# 15_HEATER.net
KiCad netlist of a schematic drawn in Altium Designer
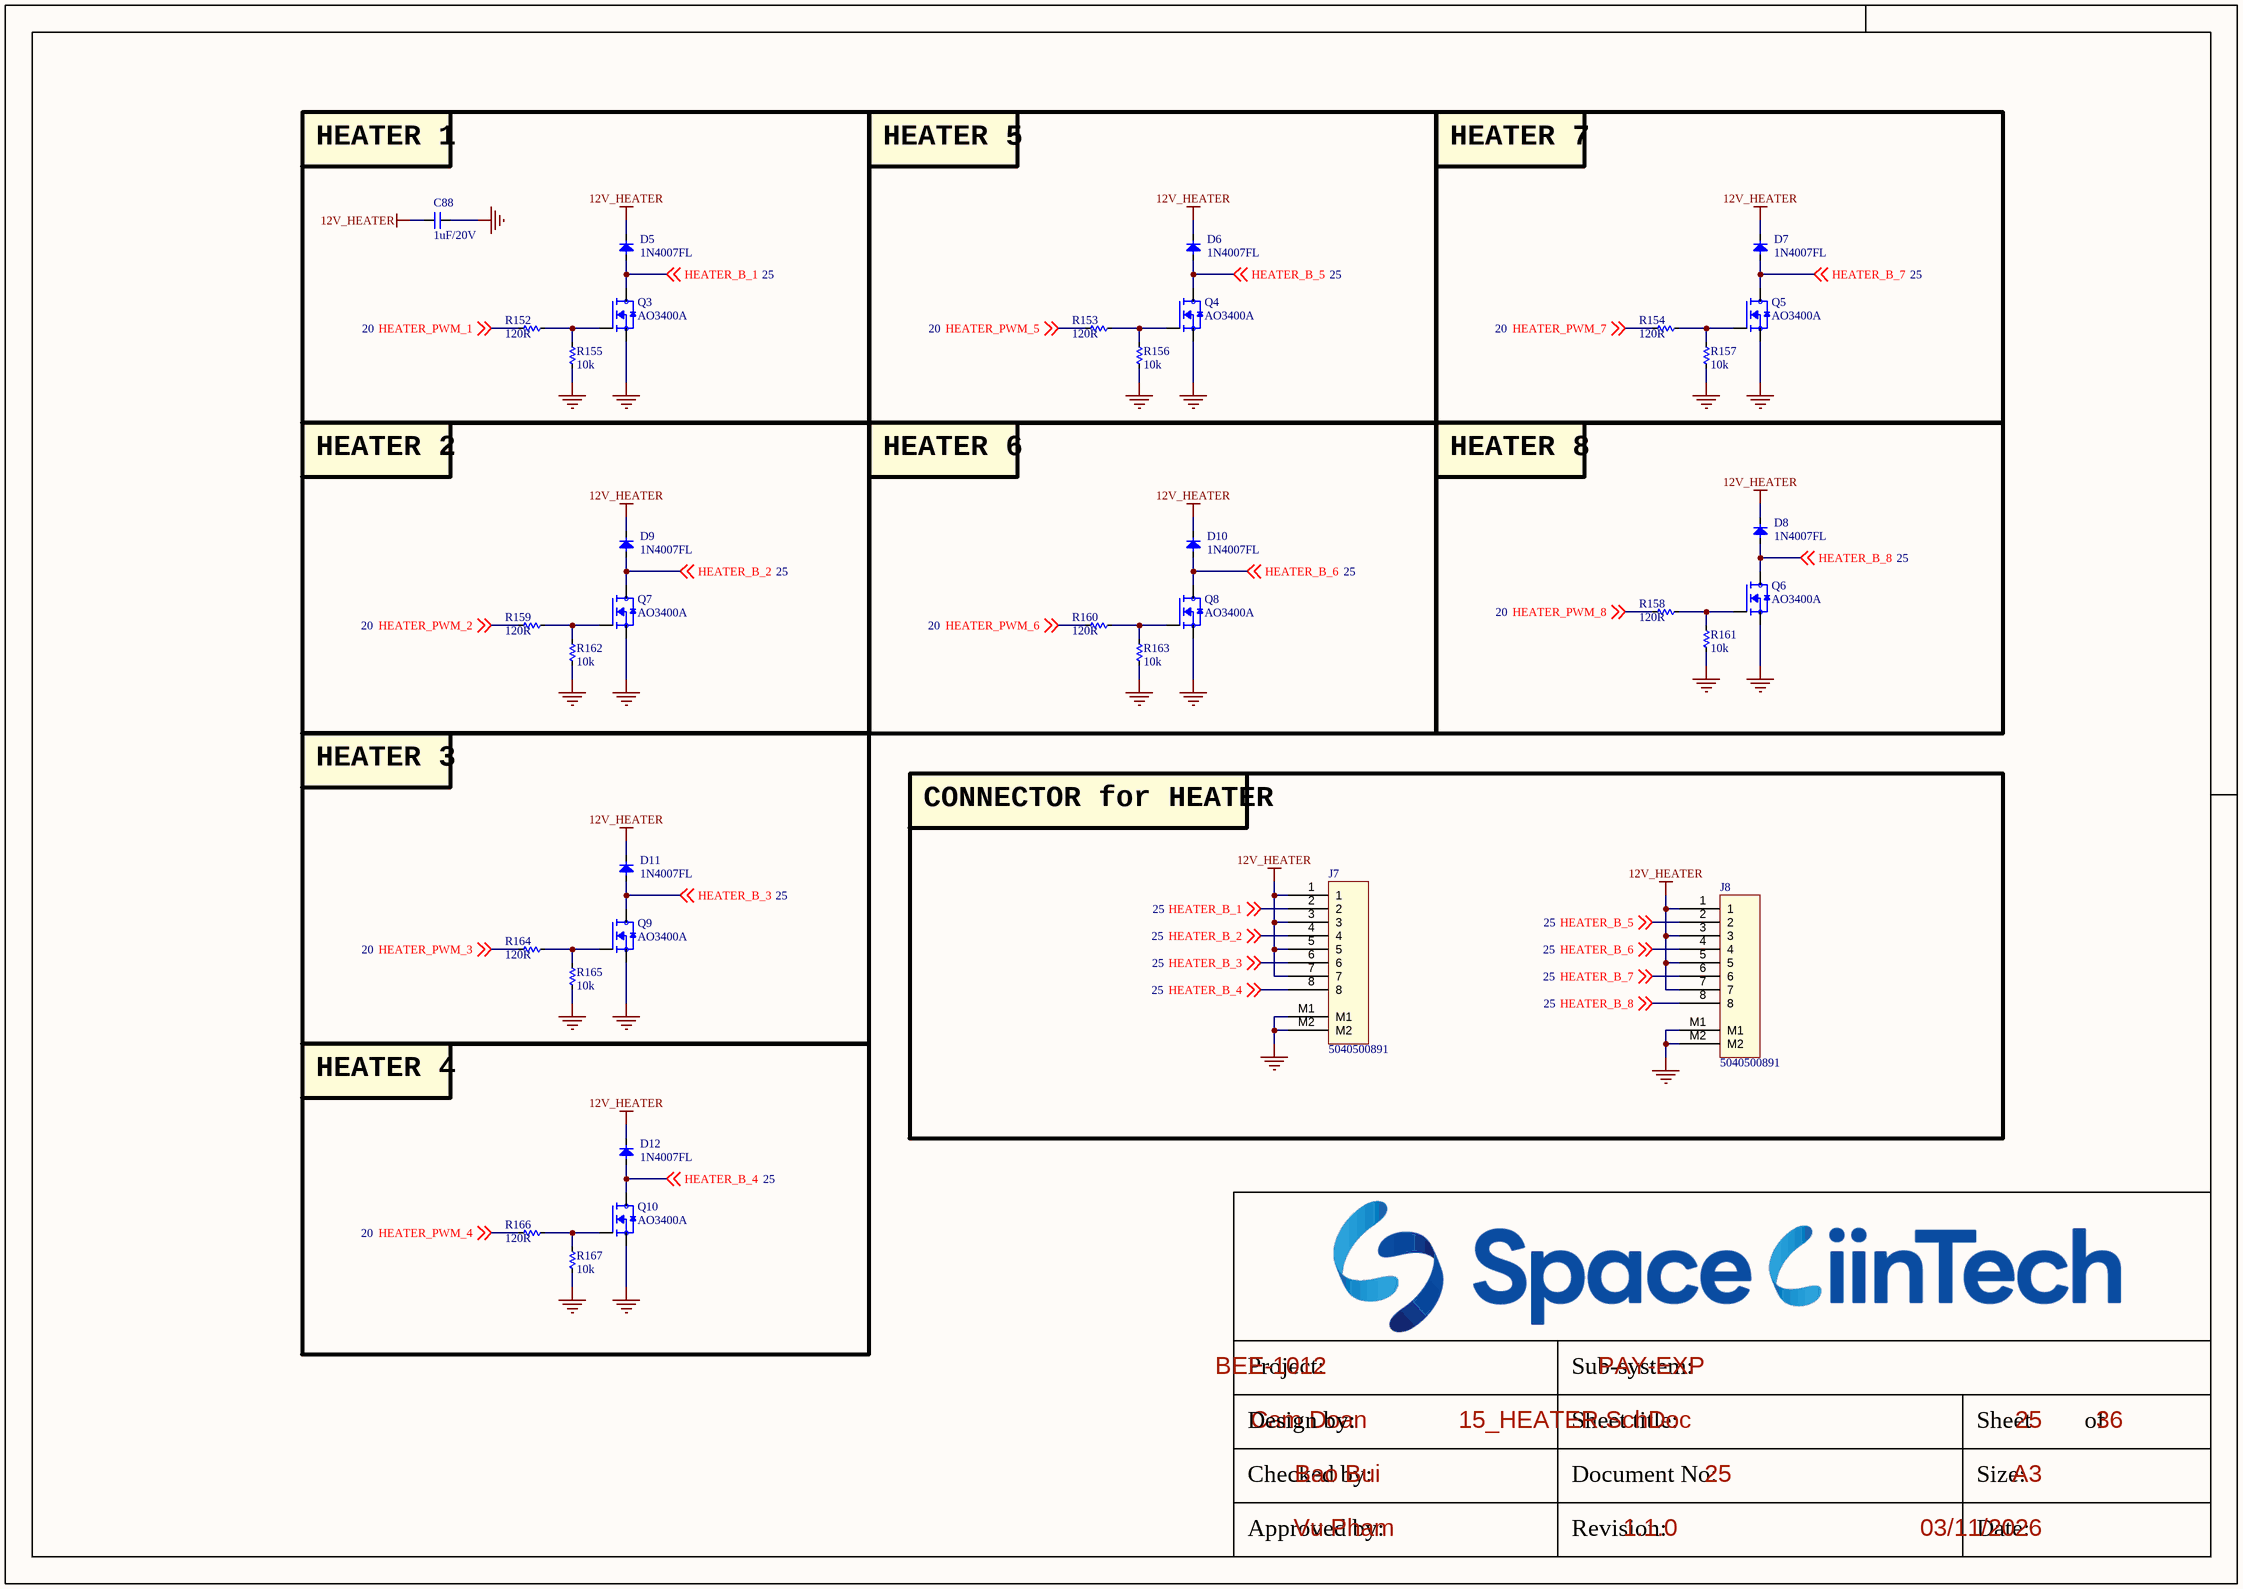
[diagram p0: 15_HEATER.SchDoc]

(export (version "E")
  (design (tool "Eeschema 10.0.6"))
  (components
    (comp (ref "C88")
      (value "1uF/20V")
      (footprint "CAP_C_1005X50_L")
      (description "CAP")
      (libsource (lib "LABLIB") (part "_CAP_C_2"))
    )
    (comp (ref "D5")
      (value "1N4007FL")
      (footprint "SOD3717X145N")
      (description "Default Diode")
      (fields (field (name "PUBLISHER") "Altium Limited"))
      (libsource (lib "LABLIB") (part "Diode SMD"))
    )
    (comp (ref "D6")
      (value "1N4007FL")
      (footprint "SOD3717X145N")
      (description "Default Diode")
      (fields (field (name "PUBLISHER") "Altium Limited"))
      (libsource (lib "LABLIB") (part "Diode SMD"))
    )
    (comp (ref "D7")
      (value "1N4007FL")
      (footprint "SOD3717X145N")
      (description "Default Diode")
      (fields (field (name "PUBLISHER") "Altium Limited"))
      (libsource (lib "LABLIB") (part "Diode SMD"))
    )
    (comp (ref "D8")
      (value "1N4007FL")
      (footprint "SOD3717X145N")
      (description "Default Diode")
      (fields (field (name "PUBLISHER") "Altium Limited"))
      (libsource (lib "LABLIB") (part "Diode SMD"))
    )
    (comp (ref "D9")
      (value "1N4007FL")
      (footprint "SOD3717X145N")
      (description "Default Diode")
      (fields (field (name "PUBLISHER") "Altium Limited"))
      (libsource (lib "LABLIB") (part "Diode SMD"))
    )
    (comp (ref "D10")
      (value "1N4007FL")
      (footprint "SOD3717X145N")
      (description "Default Diode")
      (fields (field (name "PUBLISHER") "Altium Limited"))
      (libsource (lib "LABLIB") (part "Diode SMD"))
    )
    (comp (ref "D11")
      (value "1N4007FL")
      (footprint "SOD3717X145N")
      (description "Default Diode")
      (fields (field (name "PUBLISHER") "Altium Limited"))
      (libsource (lib "LABLIB") (part "Diode SMD"))
    )
    (comp (ref "D12")
      (value "1N4007FL")
      (footprint "SOD3717X145N")
      (description "Default Diode")
      (fields (field (name "PUBLISHER") "Altium Limited"))
      (libsource (lib "LABLIB") (part "Diode SMD"))
    )
    (comp (ref "J7")
      (value "5040500891")
      (footprint "MOLEX_5040500891")
      (libsource (lib "LABLIB") (part "Header 8x1_2M"))
    )
    (comp (ref "J8")
      (value "5040500891")
      (footprint "MOLEX_5040500891")
      (libsource (lib "LABLIB") (part "Header 8x1_2M"))
    )
    (comp (ref "Q3")
      (value "AO3400A")
      (footprint "SOT95P240X120-3N")
      (description "N-Channel 30 V 5.7A (Ta) 1.4W (Ta) Surface Mount SOT-23-3")
      (fields (field (name "MF") "Alpha & Omega Semiconductor"))
      (libsource (lib "LABLIB") (part "MOSFET_N"))
    )
    (comp (ref "Q4")
      (value "AO3400A")
      (footprint "SOT95P240X120-3N")
      (description "N-Channel 30 V 5.7A (Ta) 1.4W (Ta) Surface Mount SOT-23-3")
      (fields (field (name "MF") "Alpha & Omega Semiconductor"))
      (libsource (lib "LABLIB") (part "MOSFET_N"))
    )
    (comp (ref "Q5")
      (value "AO3400A")
      (footprint "SOT95P240X120-3N")
      (description "N-Channel 30 V 5.7A (Ta) 1.4W (Ta) Surface Mount SOT-23-3")
      (fields (field (name "MF") "Alpha & Omega Semiconductor"))
      (libsource (lib "LABLIB") (part "MOSFET_N"))
    )
    (comp (ref "Q6")
      (value "AO3400A")
      (footprint "SOT95P240X120-3N")
      (description "N-Channel 30 V 5.7A (Ta) 1.4W (Ta) Surface Mount SOT-23-3")
      (fields (field (name "MF") "Alpha & Omega Semiconductor"))
      (libsource (lib "LABLIB") (part "MOSFET_N"))
    )
    (comp (ref "Q7")
      (value "AO3400A")
      (footprint "SOT95P240X120-3N")
      (description "N-Channel 30 V 5.7A (Ta) 1.4W (Ta) Surface Mount SOT-23-3")
      (fields (field (name "MF") "Alpha & Omega Semiconductor"))
      (libsource (lib "LABLIB") (part "MOSFET_N"))
    )
    (comp (ref "Q8")
      (value "AO3400A")
      (footprint "SOT95P240X120-3N")
      (description "N-Channel 30 V 5.7A (Ta) 1.4W (Ta) Surface Mount SOT-23-3")
      (fields (field (name "MF") "Alpha & Omega Semiconductor"))
      (libsource (lib "LABLIB") (part "MOSFET_N"))
    )
    (comp (ref "Q9")
      (value "AO3400A")
      (footprint "SOT95P240X120-3N")
      (description "N-Channel 30 V 5.7A (Ta) 1.4W (Ta) Surface Mount SOT-23-3")
      (fields (field (name "MF") "Alpha & Omega Semiconductor"))
      (libsource (lib "LABLIB") (part "MOSFET_N"))
    )
    (comp (ref "Q10")
      (value "AO3400A")
      (footprint "SOT95P240X120-3N")
      (description "N-Channel 30 V 5.7A (Ta) 1.4W (Ta) Surface Mount SOT-23-3")
      (fields (field (name "MF") "Alpha & Omega Semiconductor"))
      (libsource (lib "LABLIB") (part "MOSFET_N"))
    )
    (comp (ref "R152")
      (value "120R")
      (footprint "RES_C_1005x30_L")
      (description "RES")
      (libsource (lib "LABLIB") (part "_RES_B_2"))
    )
    (comp (ref "R153")
      (value "120R")
      (footprint "RES_C_1005x30_L")
      (description "RES")
      (libsource (lib "LABLIB") (part "_RES_B_2"))
    )
    (comp (ref "R154")
      (value "120R")
      (footprint "RES_C_1005x30_L")
      (description "RES")
      (libsource (lib "LABLIB") (part "_RES_B_2"))
    )
    (comp (ref "R155")
      (value "10k")
      (footprint "RES_C_1005x30_L")
      (description "RES")
      (libsource (lib "LABLIB") (part "_RES_B_2"))
    )
    (comp (ref "R156")
      (value "10k")
      (footprint "RES_C_1005x30_L")
      (description "RES")
      (libsource (lib "LABLIB") (part "_RES_B_2"))
    )
    (comp (ref "R157")
      (value "10k")
      (footprint "RES_C_1005x30_L")
      (description "RES")
      (libsource (lib "LABLIB") (part "_RES_B_2"))
    )
    (comp (ref "R158")
      (value "120R")
      (footprint "RES_C_1005x30_L")
      (description "RES")
      (libsource (lib "LABLIB") (part "_RES_B_2"))
    )
    (comp (ref "R159")
      (value "120R")
      (footprint "RES_C_1005x30_L")
      (description "RES")
      (libsource (lib "LABLIB") (part "_RES_B_2"))
    )
    (comp (ref "R160")
      (value "120R")
      (footprint "RES_C_1005x30_L")
      (description "RES")
      (libsource (lib "LABLIB") (part "_RES_B_2"))
    )
    (comp (ref "R161")
      (value "10k")
      (footprint "RES_C_1005x30_L")
      (description "RES")
      (libsource (lib "LABLIB") (part "_RES_B_2"))
    )
    (comp (ref "R162")
      (value "10k")
      (footprint "RES_C_1005x30_L")
      (description "RES")
      (libsource (lib "LABLIB") (part "_RES_B_2"))
    )
    (comp (ref "R163")
      (value "10k")
      (footprint "RES_C_1005x30_L")
      (description "RES")
      (libsource (lib "LABLIB") (part "_RES_B_2"))
    )
    (comp (ref "R164")
      (value "120R")
      (footprint "RES_C_1005x30_L")
      (description "RES")
      (libsource (lib "LABLIB") (part "_RES_B_2"))
    )
    (comp (ref "R165")
      (value "10k")
      (footprint "RES_C_1005x30_L")
      (description "RES")
      (libsource (lib "LABLIB") (part "_RES_B_2"))
    )
    (comp (ref "R166")
      (value "120R")
      (footprint "RES_C_1005x30_L")
      (description "RES")
      (libsource (lib "LABLIB") (part "_RES_B_2"))
    )
    (comp (ref "R167")
      (value "10k")
      (footprint "RES_C_1005x30_L")
      (description "RES")
      (libsource (lib "LABLIB") (part "_RES_B_2"))
    )
  )
  (nets
    (net (code "1") (name "12V_HEATER") (class "Default")
      (node (ref "C88") (pin "2") (pinfunction "2_2") (pintype "passive"))
      (node (ref "D10") (pin "1") (pinfunction "K_1") (pintype "passive"))
      (node (ref "D11") (pin "1") (pinfunction "K_1") (pintype "passive"))
      (node (ref "D12") (pin "1") (pinfunction "K_1") (pintype "passive"))
      (node (ref "D5") (pin "1") (pinfunction "K_1") (pintype "passive"))
      (node (ref "D6") (pin "1") (pinfunction "K_1") (pintype "passive"))
      (node (ref "D7") (pin "1") (pinfunction "K_1") (pintype "passive"))
      (node (ref "D8") (pin "1") (pinfunction "K_1") (pintype "passive"))
      (node (ref "D9") (pin "1") (pinfunction "K_1") (pintype "passive"))
      (node (ref "J7") (pin "1") (pinfunction "1_1") (pintype "passive"))
      (node (ref "J7") (pin "3") (pinfunction "3_3") (pintype "passive"))
      (node (ref "J7") (pin "5") (pinfunction "5_5") (pintype "passive"))
      (node (ref "J7") (pin "7") (pinfunction "7_7") (pintype "passive"))
      (node (ref "J8") (pin "1") (pinfunction "1_1") (pintype "passive"))
      (node (ref "J8") (pin "3") (pinfunction "3_3") (pintype "passive"))
      (node (ref "J8") (pin "5") (pinfunction "5_5") (pintype "passive"))
      (node (ref "J8") (pin "7") (pinfunction "7_7") (pintype "passive"))
    )
    (net (code "2") (name "GND") (class "Default")
      (node (ref "C88") (pin "1") (pinfunction "1_1") (pintype "passive"))
      (node (ref "J7") (pin "M1") (pinfunction "M1_M1") (pintype "passive"))
      (node (ref "J7") (pin "M2") (pinfunction "M2_M2") (pintype "passive"))
      (node (ref "J8") (pin "M1") (pinfunction "M1_M1") (pintype "passive"))
      (node (ref "J8") (pin "M2") (pinfunction "M2_M2") (pintype "passive"))
      (node (ref "Q10") (pin "2") (pinfunction "S_2") (pintype "passive"))
      (node (ref "Q3") (pin "2") (pinfunction "S_2") (pintype "passive"))
      (node (ref "Q4") (pin "2") (pinfunction "S_2") (pintype "passive"))
      (node (ref "Q5") (pin "2") (pinfunction "S_2") (pintype "passive"))
      (node (ref "Q6") (pin "2") (pinfunction "S_2") (pintype "passive"))
      (node (ref "Q7") (pin "2") (pinfunction "S_2") (pintype "passive"))
      (node (ref "Q8") (pin "2") (pinfunction "S_2") (pintype "passive"))
      (node (ref "Q9") (pin "2") (pinfunction "S_2") (pintype "passive"))
      (node (ref "R155") (pin "1") (pinfunction "1_1") (pintype "passive"))
      (node (ref "R156") (pin "1") (pinfunction "1_1") (pintype "passive"))
      (node (ref "R157") (pin "1") (pinfunction "1_1") (pintype "passive"))
      (node (ref "R161") (pin "1") (pinfunction "1_1") (pintype "passive"))
      (node (ref "R162") (pin "1") (pinfunction "1_1") (pintype "passive"))
      (node (ref "R163") (pin "1") (pinfunction "1_1") (pintype "passive"))
      (node (ref "R165") (pin "1") (pinfunction "1_1") (pintype "passive"))
      (node (ref "R167") (pin "1") (pinfunction "1_1") (pintype "passive"))
    )
    (net (code "3") (name "HEATER_B_1") (class "Default")
      (node (ref "D5") (pin "2") (pinfunction "A_2") (pintype "passive"))
      (node (ref "J7") (pin "2") (pinfunction "2_2") (pintype "passive"))
      (node (ref "Q3") (pin "3") (pinfunction "D_3") (pintype "passive"))
    )
    (net (code "4") (name "HEATER_B_2") (class "Default")
      (node (ref "D9") (pin "2") (pinfunction "A_2") (pintype "passive"))
      (node (ref "J7") (pin "4") (pinfunction "4_4") (pintype "passive"))
      (node (ref "Q7") (pin "3") (pinfunction "D_3") (pintype "passive"))
    )
    (net (code "5") (name "HEATER_B_3") (class "Default")
      (node (ref "D11") (pin "2") (pinfunction "A_2") (pintype "passive"))
      (node (ref "J7") (pin "6") (pinfunction "6_6") (pintype "passive"))
      (node (ref "Q9") (pin "3") (pinfunction "D_3") (pintype "passive"))
    )
    (net (code "6") (name "HEATER_B_4") (class "Default")
      (node (ref "D12") (pin "2") (pinfunction "A_2") (pintype "passive"))
      (node (ref "J7") (pin "8") (pinfunction "8_8") (pintype "passive"))
      (node (ref "Q10") (pin "3") (pinfunction "D_3") (pintype "passive"))
    )
    (net (code "7") (name "HEATER_B_5") (class "Default")
      (node (ref "D6") (pin "2") (pinfunction "A_2") (pintype "passive"))
      (node (ref "J8") (pin "2") (pinfunction "2_2") (pintype "passive"))
      (node (ref "Q4") (pin "3") (pinfunction "D_3") (pintype "passive"))
    )
    (net (code "8") (name "HEATER_B_6") (class "Default")
      (node (ref "D10") (pin "2") (pinfunction "A_2") (pintype "passive"))
      (node (ref "J8") (pin "4") (pinfunction "4_4") (pintype "passive"))
      (node (ref "Q8") (pin "3") (pinfunction "D_3") (pintype "passive"))
    )
    (net (code "9") (name "HEATER_B_7") (class "Default")
      (node (ref "D7") (pin "2") (pinfunction "A_2") (pintype "passive"))
      (node (ref "J8") (pin "6") (pinfunction "6_6") (pintype "passive"))
      (node (ref "Q5") (pin "3") (pinfunction "D_3") (pintype "passive"))
    )
    (net (code "10") (name "HEATER_B_8") (class "Default")
      (node (ref "D8") (pin "2") (pinfunction "A_2") (pintype "passive"))
      (node (ref "J8") (pin "8") (pinfunction "8_8") (pintype "passive"))
      (node (ref "Q6") (pin "3") (pinfunction "D_3") (pintype "passive"))
    )
    (net (code "11") (name "HEATER_PWM_1") (class "Default")
      (node (ref "R152") (pin "1") (pinfunction "1_1") (pintype "passive"))
    )
    (net (code "12") (name "HEATER_PWM_2") (class "Default")
      (node (ref "R159") (pin "1") (pinfunction "1_1") (pintype "passive"))
    )
    (net (code "13") (name "HEATER_PWM_3") (class "Default")
      (node (ref "R164") (pin "1") (pinfunction "1_1") (pintype "passive"))
    )
    (net (code "14") (name "HEATER_PWM_4") (class "Default")
      (node (ref "R166") (pin "1") (pinfunction "1_1") (pintype "passive"))
    )
    (net (code "15") (name "HEATER_PWM_5") (class "Default")
      (node (ref "R153") (pin "1") (pinfunction "1_1") (pintype "passive"))
    )
    (net (code "16") (name "HEATER_PWM_6") (class "Default")
      (node (ref "R160") (pin "1") (pinfunction "1_1") (pintype "passive"))
    )
    (net (code "17") (name "HEATER_PWM_7") (class "Default")
      (node (ref "R154") (pin "1") (pinfunction "1_1") (pintype "passive"))
    )
    (net (code "18") (name "HEATER_PWM_8") (class "Default")
      (node (ref "R158") (pin "1") (pinfunction "1_1") (pintype "passive"))
    )
    (net (code "19") (name "Net-(Q3-G)") (class "Default")
      (node (ref "Q3") (pin "1") (pinfunction "G_1") (pintype "passive"))
      (node (ref "R152") (pin "2") (pinfunction "2_2") (pintype "passive"))
      (node (ref "R155") (pin "2") (pinfunction "2_2") (pintype "passive"))
    )
    (net (code "20") (name "Net-(Q4-G)") (class "Default")
      (node (ref "Q4") (pin "1") (pinfunction "G_1") (pintype "passive"))
      (node (ref "R153") (pin "2") (pinfunction "2_2") (pintype "passive"))
      (node (ref "R156") (pin "2") (pinfunction "2_2") (pintype "passive"))
    )
    (net (code "21") (name "Net-(Q5-G)") (class "Default")
      (node (ref "Q5") (pin "1") (pinfunction "G_1") (pintype "passive"))
      (node (ref "R154") (pin "2") (pinfunction "2_2") (pintype "passive"))
      (node (ref "R157") (pin "2") (pinfunction "2_2") (pintype "passive"))
    )
    (net (code "22") (name "Net-(Q6-G)") (class "Default")
      (node (ref "Q6") (pin "1") (pinfunction "G_1") (pintype "passive"))
      (node (ref "R158") (pin "2") (pinfunction "2_2") (pintype "passive"))
      (node (ref "R161") (pin "2") (pinfunction "2_2") (pintype "passive"))
    )
    (net (code "23") (name "Net-(Q7-G)") (class "Default")
      (node (ref "Q7") (pin "1") (pinfunction "G_1") (pintype "passive"))
      (node (ref "R159") (pin "2") (pinfunction "2_2") (pintype "passive"))
      (node (ref "R162") (pin "2") (pinfunction "2_2") (pintype "passive"))
    )
    (net (code "24") (name "Net-(Q8-G)") (class "Default")
      (node (ref "Q8") (pin "1") (pinfunction "G_1") (pintype "passive"))
      (node (ref "R160") (pin "2") (pinfunction "2_2") (pintype "passive"))
      (node (ref "R163") (pin "2") (pinfunction "2_2") (pintype "passive"))
    )
    (net (code "25") (name "Net-(Q9-G)") (class "Default")
      (node (ref "Q9") (pin "1") (pinfunction "G_1") (pintype "passive"))
      (node (ref "R164") (pin "2") (pinfunction "2_2") (pintype "passive"))
      (node (ref "R165") (pin "2") (pinfunction "2_2") (pintype "passive"))
    )
    (net (code "26") (name "Net-(Q10-G)") (class "Default")
      (node (ref "Q10") (pin "1") (pinfunction "G_1") (pintype "passive"))
      (node (ref "R166") (pin "2") (pinfunction "2_2") (pintype "passive"))
      (node (ref "R167") (pin "2") (pinfunction "2_2") (pintype "passive"))
    )
  )
)
